# alu_slice.net
KiCad netlist of a schematic drawn in EAGLE
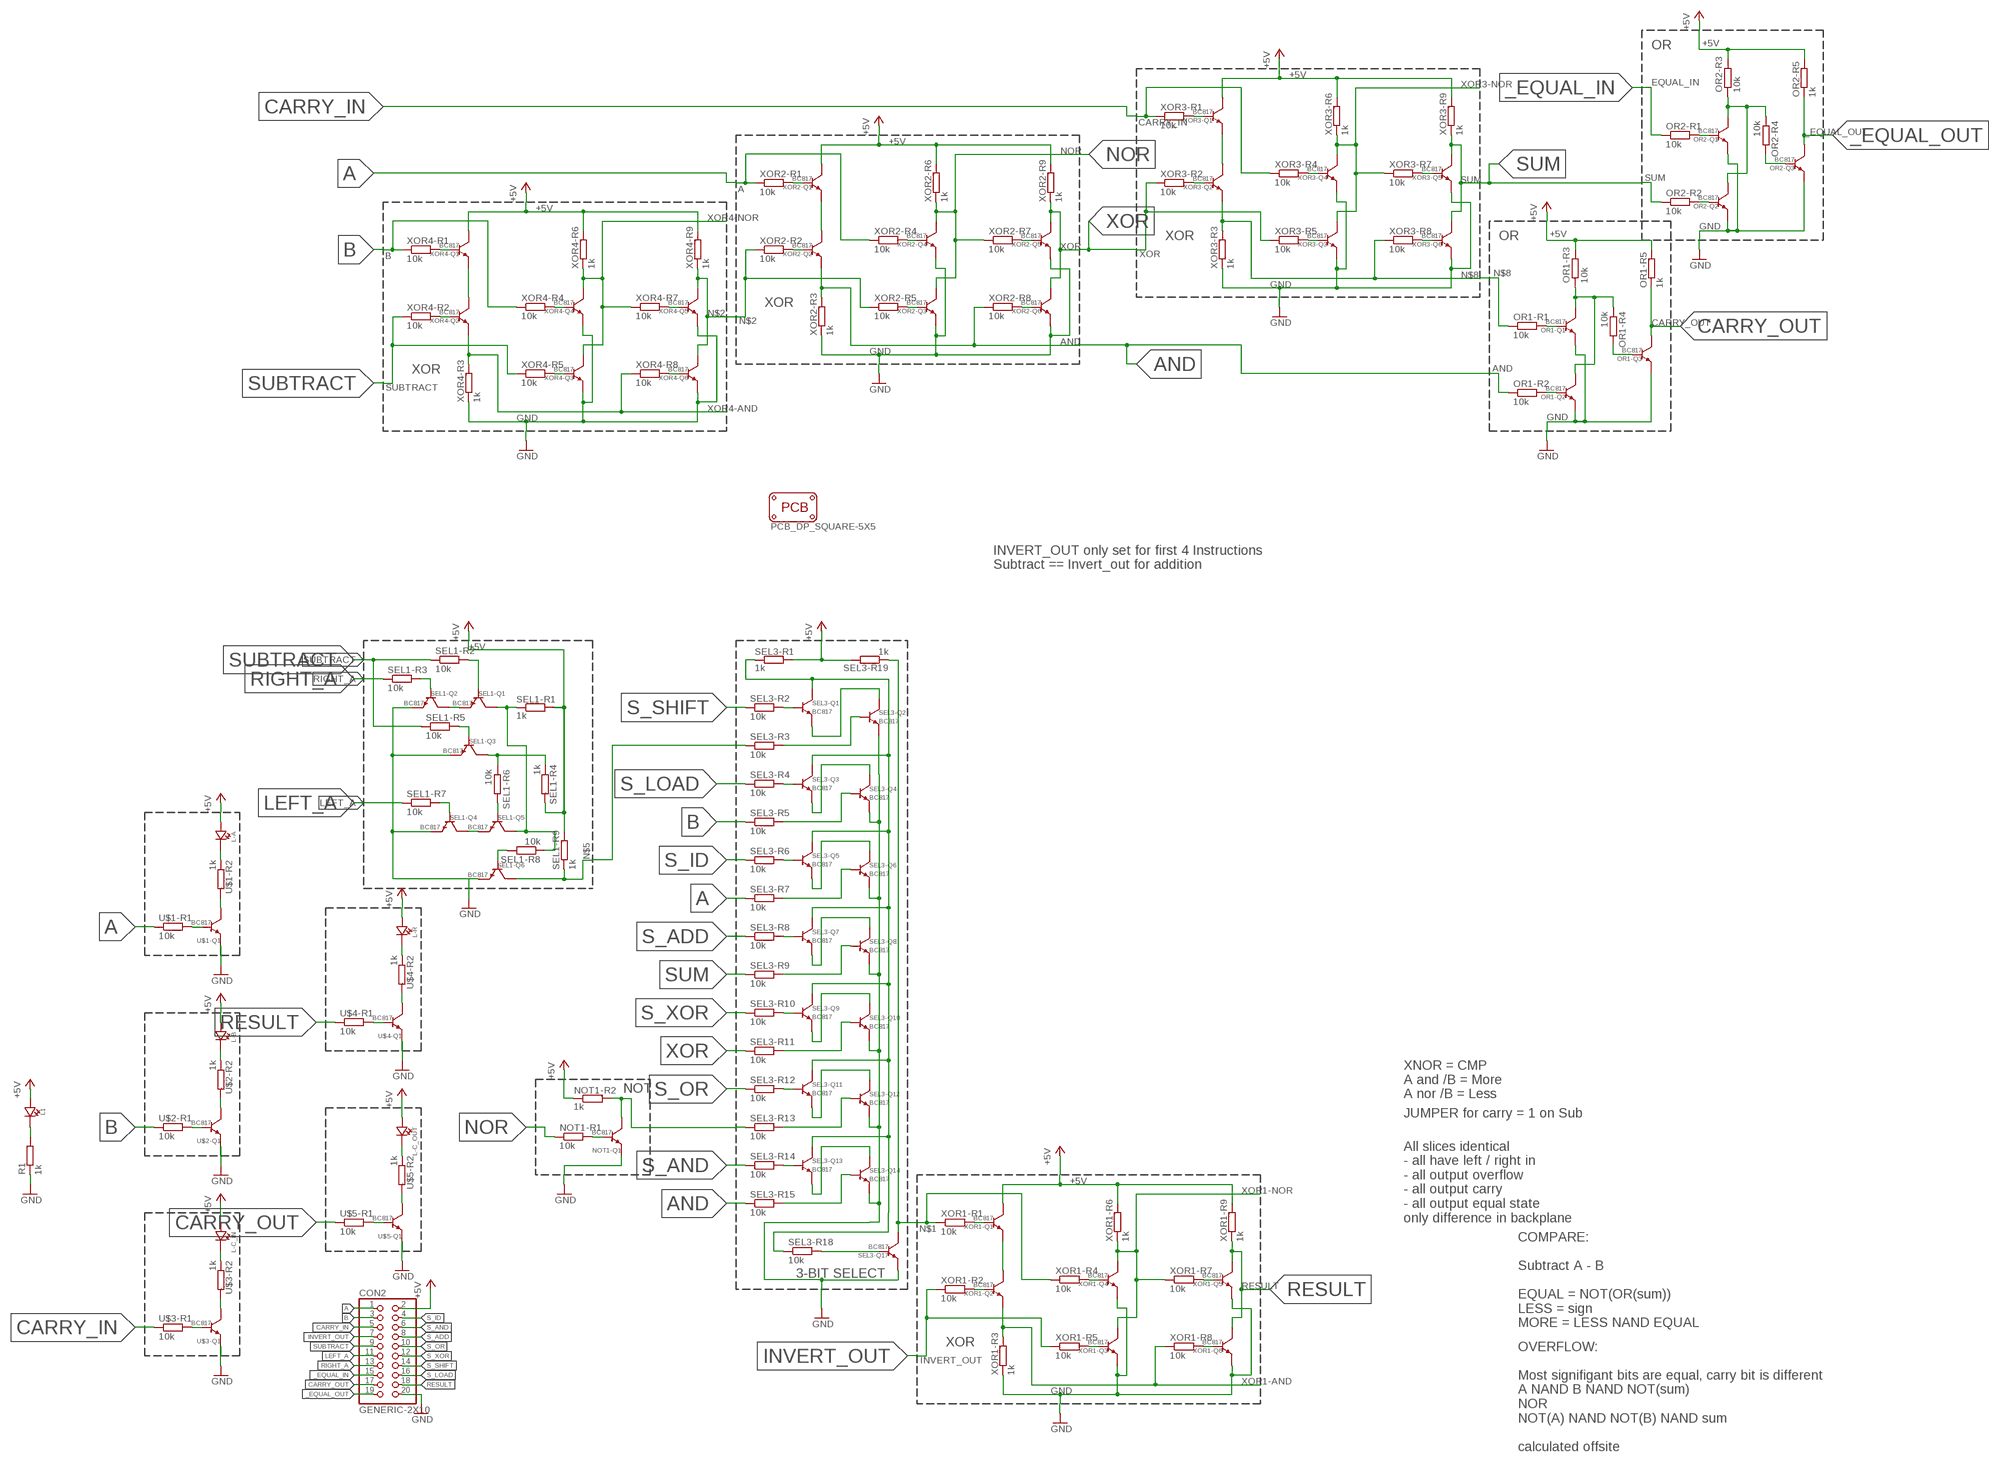
[diagram p0: schematic, sheet 1]

(export (version "E")
  (design (tool "Eeschema 10.0.6"))
  (components
    (comp (ref "CON2")
      (value "GENERIC-2X10")
      (footprint "eagle-import:PINHEADER-100MIL-2X10-EDGE")
      (libsource (lib "eagle-import") (part "GENERIC-2X10"))
    )
    (comp (ref "L-A")
      (value "LED0603")
      (footprint "eagle-import:CHIPLED_0603")
      (libsource (lib "eagle-import") (part "LED0603"))
    )
    (comp (ref "L-B")
      (value "LED0603")
      (footprint "eagle-import:CHIPLED_0603")
      (libsource (lib "eagle-import") (part "LED0603"))
    )
    (comp (ref "L-C_IN")
      (value "LED0603")
      (footprint "eagle-import:CHIPLED_0603")
      (libsource (lib "eagle-import") (part "LED0603"))
    )
    (comp (ref "L-C_OUT")
      (value "LED0603")
      (footprint "eagle-import:CHIPLED_0603")
      (libsource (lib "eagle-import") (part "LED0603"))
    )
    (comp (ref "L-R")
      (value "LED0603")
      (footprint "eagle-import:CHIPLED_0603")
      (libsource (lib "eagle-import") (part "LED0603"))
    )
    (comp (ref "L1")
      (value "LED0805")
      (footprint "eagle-import:CHIPLED_0805")
      (libsource (lib "eagle-import") (part "LED0805"))
    )
    (comp (ref "NOT1-Q1")
      (value "BC817")
      (footprint "eagle-import:SOT23")
      (libsource (lib "eagle-import") (part "TRANSISTOR-NPN-GENERIC-SOT23-BECDEFAULT"))
    )
    (comp (ref "NOT1-R1")
      (value "10k")
      (footprint "eagle-import:R0603")
      (libsource (lib "eagle-import") (part "R-EU_R0603"))
    )
    (comp (ref "NOT1-R2")
      (value "1k")
      (footprint "eagle-import:R0603-MARK")
      (libsource (lib "eagle-import") (part "R-EU-MARKEDR0603"))
    )
    (comp (ref "OR1-Q1")
      (value "BC817")
      (footprint "eagle-import:SOT23")
      (libsource (lib "eagle-import") (part "TRANSISTOR-NPN-GENERIC-SOT23-BECDEFAULT"))
    )
    (comp (ref "OR1-Q2")
      (value "BC817")
      (footprint "eagle-import:SOT23")
      (libsource (lib "eagle-import") (part "TRANSISTOR-NPN-GENERIC-SOT23-BECDEFAULT"))
    )
    (comp (ref "OR1-Q3")
      (value "BC817")
      (footprint "eagle-import:SOT23")
      (libsource (lib "eagle-import") (part "TRANSISTOR-NPN-GENERIC-SOT23-BECDEFAULT"))
    )
    (comp (ref "OR1-R1")
      (value "10k")
      (footprint "eagle-import:R0603")
      (libsource (lib "eagle-import") (part "R-EU_R0603"))
    )
    (comp (ref "OR1-R2")
      (value "10k")
      (footprint "eagle-import:R0603")
      (libsource (lib "eagle-import") (part "R-EU_R0603"))
    )
    (comp (ref "OR1-R3")
      (value "10k")
      (footprint "eagle-import:R0603")
      (libsource (lib "eagle-import") (part "R-EU_R0603"))
    )
    (comp (ref "OR1-R4")
      (value "10k")
      (footprint "eagle-import:R0603")
      (libsource (lib "eagle-import") (part "R-EU_R0603"))
    )
    (comp (ref "OR1-R5")
      (value "1k")
      (footprint "eagle-import:R0603-MARK")
      (libsource (lib "eagle-import") (part "R-EU-MARKEDR0603"))
    )
    (comp (ref "OR2-Q1")
      (value "BC817")
      (footprint "eagle-import:SOT23")
      (libsource (lib "eagle-import") (part "TRANSISTOR-NPN-GENERIC-SOT23-BECDEFAULT"))
    )
    (comp (ref "OR2-Q2")
      (value "BC817")
      (footprint "eagle-import:SOT23")
      (libsource (lib "eagle-import") (part "TRANSISTOR-NPN-GENERIC-SOT23-BECDEFAULT"))
    )
    (comp (ref "OR2-Q3")
      (value "BC817")
      (footprint "eagle-import:SOT23")
      (libsource (lib "eagle-import") (part "TRANSISTOR-NPN-GENERIC-SOT23-BECDEFAULT"))
    )
    (comp (ref "OR2-R1")
      (value "10k")
      (footprint "eagle-import:R0603")
      (libsource (lib "eagle-import") (part "R-EU_R0603"))
    )
    (comp (ref "OR2-R2")
      (value "10k")
      (footprint "eagle-import:R0603")
      (libsource (lib "eagle-import") (part "R-EU_R0603"))
    )
    (comp (ref "OR2-R3")
      (value "10k")
      (footprint "eagle-import:R0603")
      (libsource (lib "eagle-import") (part "R-EU_R0603"))
    )
    (comp (ref "OR2-R4")
      (value "10k")
      (footprint "eagle-import:R0603")
      (libsource (lib "eagle-import") (part "R-EU_R0603"))
    )
    (comp (ref "OR2-R5")
      (value "1k")
      (footprint "eagle-import:R0603-MARK")
      (libsource (lib "eagle-import") (part "R-EU-MARKEDR0603"))
    )
    (comp (ref "PCB1")
      (value "PCB_DP_SQUARE-5X5")
      (footprint "eagle-import:DP5050_V1")
      (libsource (lib "eagle-import") (part "PCB_DP_SQUARE-5X5"))
    )
    (comp (ref "R1")
      (value "1k")
      (footprint "eagle-import:R0603-MARK")
      (libsource (lib "eagle-import") (part "R-EU-MARKEDR0603"))
    )
    (comp (ref "SEL1-Q1")
      (value "BC817")
      (footprint "eagle-import:SOT23")
      (libsource (lib "eagle-import") (part "TRANSISTOR-NPN-GENERIC-SOT23-BECDEFAULT"))
    )
    (comp (ref "SEL1-Q2")
      (value "BC817")
      (footprint "eagle-import:SOT23")
      (libsource (lib "eagle-import") (part "TRANSISTOR-NPN-GENERIC-SOT23-BECDEFAULT"))
    )
    (comp (ref "SEL1-Q3")
      (value "BC817")
      (footprint "eagle-import:SOT23")
      (libsource (lib "eagle-import") (part "TRANSISTOR-NPN-GENERIC-SOT23-BECDEFAULT"))
    )
    (comp (ref "SEL1-Q4")
      (value "BC817")
      (footprint "eagle-import:SOT23")
      (libsource (lib "eagle-import") (part "TRANSISTOR-NPN-GENERIC-SOT23-BECDEFAULT"))
    )
    (comp (ref "SEL1-Q5")
      (value "BC817")
      (footprint "eagle-import:SOT23")
      (libsource (lib "eagle-import") (part "TRANSISTOR-NPN-GENERIC-SOT23-BECDEFAULT"))
    )
    (comp (ref "SEL1-Q6")
      (value "BC817")
      (footprint "eagle-import:SOT23")
      (libsource (lib "eagle-import") (part "TRANSISTOR-NPN-GENERIC-SOT23-BECDEFAULT"))
    )
    (comp (ref "SEL1-R1")
      (value "1k")
      (footprint "eagle-import:R0603-MARK")
      (libsource (lib "eagle-import") (part "R-EU-MARKEDR0603"))
    )
    (comp (ref "SEL1-R2")
      (value "10k")
      (footprint "eagle-import:R0603")
      (libsource (lib "eagle-import") (part "R-EU_R0603"))
    )
    (comp (ref "SEL1-R3")
      (value "10k")
      (footprint "eagle-import:R0603")
      (libsource (lib "eagle-import") (part "R-EU_R0603"))
    )
    (comp (ref "SEL1-R4")
      (value "1k")
      (footprint "eagle-import:R0603-MARK")
      (libsource (lib "eagle-import") (part "R-EU-MARKEDR0603"))
    )
    (comp (ref "SEL1-R5")
      (value "10k")
      (footprint "eagle-import:R0603")
      (libsource (lib "eagle-import") (part "R-EU_R0603"))
    )
    (comp (ref "SEL1-R6")
      (value "10k")
      (footprint "eagle-import:R0603")
      (libsource (lib "eagle-import") (part "R-EU_R0603"))
    )
    (comp (ref "SEL1-R7")
      (value "10k")
      (footprint "eagle-import:R0603")
      (libsource (lib "eagle-import") (part "R-EU_R0603"))
    )
    (comp (ref "SEL1-R8")
      (value "10k")
      (footprint "eagle-import:R0603")
      (libsource (lib "eagle-import") (part "R-EU_R0603"))
    )
    (comp (ref "SEL1-R9")
      (value "1k")
      (footprint "eagle-import:R0603-MARK")
      (libsource (lib "eagle-import") (part "R-EU-MARKEDR0603"))
    )
    (comp (ref "SEL3-Q1")
      (value "BC817")
      (footprint "eagle-import:SOT23")
      (libsource (lib "eagle-import") (part "TRANSISTOR-NPN-GENERIC-SOT23-BECDEFAULT"))
    )
    (comp (ref "SEL3-Q2")
      (value "BC817")
      (footprint "eagle-import:SOT23")
      (libsource (lib "eagle-import") (part "TRANSISTOR-NPN-GENERIC-SOT23-BECDEFAULT"))
    )
    (comp (ref "SEL3-Q3")
      (value "BC817")
      (footprint "eagle-import:SOT23")
      (libsource (lib "eagle-import") (part "TRANSISTOR-NPN-GENERIC-SOT23-BECDEFAULT"))
    )
    (comp (ref "SEL3-Q4")
      (value "BC817")
      (footprint "eagle-import:SOT23")
      (libsource (lib "eagle-import") (part "TRANSISTOR-NPN-GENERIC-SOT23-BECDEFAULT"))
    )
    (comp (ref "SEL3-Q5")
      (value "BC817")
      (footprint "eagle-import:SOT23")
      (libsource (lib "eagle-import") (part "TRANSISTOR-NPN-GENERIC-SOT23-BECDEFAULT"))
    )
    (comp (ref "SEL3-Q6")
      (value "BC817")
      (footprint "eagle-import:SOT23")
      (libsource (lib "eagle-import") (part "TRANSISTOR-NPN-GENERIC-SOT23-BECDEFAULT"))
    )
    (comp (ref "SEL3-Q7")
      (value "BC817")
      (footprint "eagle-import:SOT23")
      (libsource (lib "eagle-import") (part "TRANSISTOR-NPN-GENERIC-SOT23-BECDEFAULT"))
    )
    (comp (ref "SEL3-Q8")
      (value "BC817")
      (footprint "eagle-import:SOT23")
      (libsource (lib "eagle-import") (part "TRANSISTOR-NPN-GENERIC-SOT23-BECDEFAULT"))
    )
    (comp (ref "SEL3-Q9")
      (value "BC817")
      (footprint "eagle-import:SOT23")
      (libsource (lib "eagle-import") (part "TRANSISTOR-NPN-GENERIC-SOT23-BECDEFAULT"))
    )
    (comp (ref "SEL3-Q10")
      (value "BC817")
      (footprint "eagle-import:SOT23")
      (libsource (lib "eagle-import") (part "TRANSISTOR-NPN-GENERIC-SOT23-BECDEFAULT"))
    )
    (comp (ref "SEL3-Q11")
      (value "BC817")
      (footprint "eagle-import:SOT23")
      (libsource (lib "eagle-import") (part "TRANSISTOR-NPN-GENERIC-SOT23-BECDEFAULT"))
    )
    (comp (ref "SEL3-Q12")
      (value "BC817")
      (footprint "eagle-import:SOT23")
      (libsource (lib "eagle-import") (part "TRANSISTOR-NPN-GENERIC-SOT23-BECDEFAULT"))
    )
    (comp (ref "SEL3-Q13")
      (value "BC817")
      (footprint "eagle-import:SOT23")
      (libsource (lib "eagle-import") (part "TRANSISTOR-NPN-GENERIC-SOT23-BECDEFAULT"))
    )
    (comp (ref "SEL3-Q14")
      (value "BC817")
      (footprint "eagle-import:SOT23")
      (libsource (lib "eagle-import") (part "TRANSISTOR-NPN-GENERIC-SOT23-BECDEFAULT"))
    )
    (comp (ref "SEL3-Q17")
      (value "BC817")
      (footprint "eagle-import:SOT23")
      (libsource (lib "eagle-import") (part "TRANSISTOR-NPN-GENERIC-SOT23-BECDEFAULT"))
    )
    (comp (ref "SEL3-R1")
      (value "1k")
      (footprint "eagle-import:R0603-MARK")
      (libsource (lib "eagle-import") (part "R-EU-MARKEDR0603"))
    )
    (comp (ref "SEL3-R2")
      (value "10k")
      (footprint "eagle-import:R0603")
      (libsource (lib "eagle-import") (part "R-EU_R0603"))
    )
    (comp (ref "SEL3-R3")
      (value "10k")
      (footprint "eagle-import:R0603")
      (libsource (lib "eagle-import") (part "R-EU_R0603"))
    )
    (comp (ref "SEL3-R4")
      (value "10k")
      (footprint "eagle-import:R0603")
      (libsource (lib "eagle-import") (part "R-EU_R0603"))
    )
    (comp (ref "SEL3-R5")
      (value "10k")
      (footprint "eagle-import:R0603")
      (libsource (lib "eagle-import") (part "R-EU_R0603"))
    )
    (comp (ref "SEL3-R6")
      (value "10k")
      (footprint "eagle-import:R0603")
      (libsource (lib "eagle-import") (part "R-EU_R0603"))
    )
    (comp (ref "SEL3-R7")
      (value "10k")
      (footprint "eagle-import:R0603")
      (libsource (lib "eagle-import") (part "R-EU_R0603"))
    )
    (comp (ref "SEL3-R8")
      (value "10k")
      (footprint "eagle-import:R0603")
      (libsource (lib "eagle-import") (part "R-EU_R0603"))
    )
    (comp (ref "SEL3-R9")
      (value "10k")
      (footprint "eagle-import:R0603")
      (libsource (lib "eagle-import") (part "R-EU_R0603"))
    )
    (comp (ref "SEL3-R10")
      (value "10k")
      (footprint "eagle-import:R0603")
      (libsource (lib "eagle-import") (part "R-EU_R0603"))
    )
    (comp (ref "SEL3-R11")
      (value "10k")
      (footprint "eagle-import:R0603")
      (libsource (lib "eagle-import") (part "R-EU_R0603"))
    )
    (comp (ref "SEL3-R12")
      (value "10k")
      (footprint "eagle-import:R0603")
      (libsource (lib "eagle-import") (part "R-EU_R0603"))
    )
    (comp (ref "SEL3-R13")
      (value "10k")
      (footprint "eagle-import:R0603")
      (libsource (lib "eagle-import") (part "R-EU_R0603"))
    )
    (comp (ref "SEL3-R14")
      (value "10k")
      (footprint "eagle-import:R0603")
      (libsource (lib "eagle-import") (part "R-EU_R0603"))
    )
    (comp (ref "SEL3-R15")
      (value "10k")
      (footprint "eagle-import:R0603")
      (libsource (lib "eagle-import") (part "R-EU_R0603"))
    )
    (comp (ref "SEL3-R18")
      (value "10k")
      (footprint "eagle-import:R0603")
      (libsource (lib "eagle-import") (part "R-EU_R0603"))
    )
    (comp (ref "SEL3-R19")
      (value "1k")
      (footprint "eagle-import:R0603-MARK")
      (libsource (lib "eagle-import") (part "R-EU-MARKEDR0603"))
    )
    (comp (ref "U$1-Q1")
      (value "BC817")
      (footprint "eagle-import:SOT23")
      (libsource (lib "eagle-import") (part "TRANSISTOR-NPN-GENERIC-SOT23-BECDEFAULT"))
    )
    (comp (ref "U$1-R1")
      (value "10k")
      (footprint "eagle-import:R0603")
      (libsource (lib "eagle-import") (part "R-EU_R0603"))
    )
    (comp (ref "U$1-R2")
      (value "1k")
      (footprint "eagle-import:R0603-MARK")
      (libsource (lib "eagle-import") (part "R-EU-MARKEDR0603"))
    )
    (comp (ref "U$2-Q1")
      (value "BC817")
      (footprint "eagle-import:SOT23")
      (libsource (lib "eagle-import") (part "TRANSISTOR-NPN-GENERIC-SOT23-BECDEFAULT"))
    )
    (comp (ref "U$2-R1")
      (value "10k")
      (footprint "eagle-import:R0603")
      (libsource (lib "eagle-import") (part "R-EU_R0603"))
    )
    (comp (ref "U$2-R2")
      (value "1k")
      (footprint "eagle-import:R0603-MARK")
      (libsource (lib "eagle-import") (part "R-EU-MARKEDR0603"))
    )
    (comp (ref "U$3-Q1")
      (value "BC817")
      (footprint "eagle-import:SOT23")
      (libsource (lib "eagle-import") (part "TRANSISTOR-NPN-GENERIC-SOT23-BECDEFAULT"))
    )
    (comp (ref "U$3-R1")
      (value "10k")
      (footprint "eagle-import:R0603")
      (libsource (lib "eagle-import") (part "R-EU_R0603"))
    )
    (comp (ref "U$3-R2")
      (value "1k")
      (footprint "eagle-import:R0603-MARK")
      (libsource (lib "eagle-import") (part "R-EU-MARKEDR0603"))
    )
    (comp (ref "U$4-Q1")
      (value "BC817")
      (footprint "eagle-import:SOT23")
      (libsource (lib "eagle-import") (part "TRANSISTOR-NPN-GENERIC-SOT23-BECDEFAULT"))
    )
    (comp (ref "U$4-R1")
      (value "10k")
      (footprint "eagle-import:R0603")
      (libsource (lib "eagle-import") (part "R-EU_R0603"))
    )
    (comp (ref "U$4-R2")
      (value "1k")
      (footprint "eagle-import:R0603-MARK")
      (libsource (lib "eagle-import") (part "R-EU-MARKEDR0603"))
    )
    (comp (ref "U$5-Q1")
      (value "BC817")
      (footprint "eagle-import:SOT23")
      (libsource (lib "eagle-import") (part "TRANSISTOR-NPN-GENERIC-SOT23-BECDEFAULT"))
    )
    (comp (ref "U$5-R1")
      (value "10k")
      (footprint "eagle-import:R0603")
      (libsource (lib "eagle-import") (part "R-EU_R0603"))
    )
    (comp (ref "U$5-R2")
      (value "1k")
      (footprint "eagle-import:R0603-MARK")
      (libsource (lib "eagle-import") (part "R-EU-MARKEDR0603"))
    )
    (comp (ref "XOR1-Q1")
      (value "BC817")
      (footprint "eagle-import:SOT23")
      (libsource (lib "eagle-import") (part "TRANSISTOR-NPN-GENERIC-SOT23-BECDEFAULT"))
    )
    (comp (ref "XOR1-Q2")
      (value "BC817")
      (footprint "eagle-import:SOT23")
      (libsource (lib "eagle-import") (part "TRANSISTOR-NPN-GENERIC-SOT23-BECDEFAULT"))
    )
    (comp (ref "XOR1-Q3")
      (value "BC817")
      (footprint "eagle-import:SOT23")
      (libsource (lib "eagle-import") (part "TRANSISTOR-NPN-GENERIC-SOT23-BECDEFAULT"))
    )
    (comp (ref "XOR1-Q4")
      (value "BC817")
      (footprint "eagle-import:SOT23")
      (libsource (lib "eagle-import") (part "TRANSISTOR-NPN-GENERIC-SOT23-BECDEFAULT"))
    )
    (comp (ref "XOR1-Q5")
      (value "BC817")
      (footprint "eagle-import:SOT23")
      (libsource (lib "eagle-import") (part "TRANSISTOR-NPN-GENERIC-SOT23-BECDEFAULT"))
    )
    (comp (ref "XOR1-Q6")
      (value "BC817")
      (footprint "eagle-import:SOT23")
      (libsource (lib "eagle-import") (part "TRANSISTOR-NPN-GENERIC-SOT23-BECDEFAULT"))
    )
    (comp (ref "XOR1-R1")
      (value "10k")
      (footprint "eagle-import:R0603")
      (libsource (lib "eagle-import") (part "R-EU_R0603"))
    )
    (comp (ref "XOR1-R2")
      (value "10k")
      (footprint "eagle-import:R0603")
      (libsource (lib "eagle-import") (part "R-EU_R0603"))
    )
    (comp (ref "XOR1-R3")
      (value "1k")
      (footprint "eagle-import:R0603-MARK")
      (libsource (lib "eagle-import") (part "R-EU-MARKEDR0603"))
    )
    (comp (ref "XOR1-R4")
      (value "10k")
      (footprint "eagle-import:R0603")
      (libsource (lib "eagle-import") (part "R-EU_R0603"))
    )
    (comp (ref "XOR1-R5")
      (value "10k")
      (footprint "eagle-import:R0603")
      (libsource (lib "eagle-import") (part "R-EU_R0603"))
    )
    (comp (ref "XOR1-R6")
      (value "1k")
      (footprint "eagle-import:R0603-MARK")
      (libsource (lib "eagle-import") (part "R-EU-MARKEDR0603"))
    )
    (comp (ref "XOR1-R7")
      (value "10k")
      (footprint "eagle-import:R0603")
      (libsource (lib "eagle-import") (part "R-EU_R0603"))
    )
    (comp (ref "XOR1-R8")
      (value "10k")
      (footprint "eagle-import:R0603")
      (libsource (lib "eagle-import") (part "R-EU_R0603"))
    )
    (comp (ref "XOR1-R9")
      (value "1k")
      (footprint "eagle-import:R0603-MARK")
      (libsource (lib "eagle-import") (part "R-EU-MARKEDR0603"))
    )
    (comp (ref "XOR2-Q1")
      (value "BC817")
      (footprint "eagle-import:SOT23")
      (libsource (lib "eagle-import") (part "TRANSISTOR-NPN-GENERIC-SOT23-BECDEFAULT"))
    )
    (comp (ref "XOR2-Q2")
      (value "BC817")
      (footprint "eagle-import:SOT23")
      (libsource (lib "eagle-import") (part "TRANSISTOR-NPN-GENERIC-SOT23-BECDEFAULT"))
    )
    (comp (ref "XOR2-Q3")
      (value "BC817")
      (footprint "eagle-import:SOT23")
      (libsource (lib "eagle-import") (part "TRANSISTOR-NPN-GENERIC-SOT23-BECDEFAULT"))
    )
    (comp (ref "XOR2-Q4")
      (value "BC817")
      (footprint "eagle-import:SOT23")
      (libsource (lib "eagle-import") (part "TRANSISTOR-NPN-GENERIC-SOT23-BECDEFAULT"))
    )
    (comp (ref "XOR2-Q5")
      (value "BC817")
      (footprint "eagle-import:SOT23")
      (libsource (lib "eagle-import") (part "TRANSISTOR-NPN-GENERIC-SOT23-BECDEFAULT"))
    )
    (comp (ref "XOR2-Q6")
      (value "BC817")
      (footprint "eagle-import:SOT23")
      (libsource (lib "eagle-import") (part "TRANSISTOR-NPN-GENERIC-SOT23-BECDEFAULT"))
    )
    (comp (ref "XOR2-R1")
      (value "10k")
      (footprint "eagle-import:R0603")
      (libsource (lib "eagle-import") (part "R-EU_R0603"))
    )
    (comp (ref "XOR2-R2")
      (value "10k")
      (footprint "eagle-import:R0603")
      (libsource (lib "eagle-import") (part "R-EU_R0603"))
    )
    (comp (ref "XOR2-R3")
      (value "1k")
      (footprint "eagle-import:R0603-MARK")
      (libsource (lib "eagle-import") (part "R-EU-MARKEDR0603"))
    )
    (comp (ref "XOR2-R4")
      (value "10k")
      (footprint "eagle-import:R0603")
      (libsource (lib "eagle-import") (part "R-EU_R0603"))
    )
    (comp (ref "XOR2-R5")
      (value "10k")
      (footprint "eagle-import:R0603")
      (libsource (lib "eagle-import") (part "R-EU_R0603"))
    )
    (comp (ref "XOR2-R6")
      (value "1k")
      (footprint "eagle-import:R0603-MARK")
      (libsource (lib "eagle-import") (part "R-EU-MARKEDR0603"))
    )
    (comp (ref "XOR2-R7")
      (value "10k")
      (footprint "eagle-import:R0603")
      (libsource (lib "eagle-import") (part "R-EU_R0603"))
    )
    (comp (ref "XOR2-R8")
      (value "10k")
      (footprint "eagle-import:R0603")
      (libsource (lib "eagle-import") (part "R-EU_R0603"))
    )
    (comp (ref "XOR2-R9")
      (value "1k")
      (footprint "eagle-import:R0603-MARK")
      (libsource (lib "eagle-import") (part "R-EU-MARKEDR0603"))
    )
    (comp (ref "XOR3-Q1")
      (value "BC817")
      (footprint "eagle-import:SOT23")
      (libsource (lib "eagle-import") (part "TRANSISTOR-NPN-GENERIC-SOT23-BECDEFAULT"))
    )
    (comp (ref "XOR3-Q2")
      (value "BC817")
      (footprint "eagle-import:SOT23")
      (libsource (lib "eagle-import") (part "TRANSISTOR-NPN-GENERIC-SOT23-BECDEFAULT"))
    )
    (comp (ref "XOR3-Q3")
      (value "BC817")
      (footprint "eagle-import:SOT23")
      (libsource (lib "eagle-import") (part "TRANSISTOR-NPN-GENERIC-SOT23-BECDEFAULT"))
    )
    (comp (ref "XOR3-Q4")
      (value "BC817")
      (footprint "eagle-import:SOT23")
      (libsource (lib "eagle-import") (part "TRANSISTOR-NPN-GENERIC-SOT23-BECDEFAULT"))
    )
    (comp (ref "XOR3-Q5")
      (value "BC817")
      (footprint "eagle-import:SOT23")
      (libsource (lib "eagle-import") (part "TRANSISTOR-NPN-GENERIC-SOT23-BECDEFAULT"))
    )
    (comp (ref "XOR3-Q6")
      (value "BC817")
      (footprint "eagle-import:SOT23")
      (libsource (lib "eagle-import") (part "TRANSISTOR-NPN-GENERIC-SOT23-BECDEFAULT"))
    )
    (comp (ref "XOR3-R1")
      (value "10k")
      (footprint "eagle-import:R0603")
      (libsource (lib "eagle-import") (part "R-EU_R0603"))
    )
    (comp (ref "XOR3-R2")
      (value "10k")
      (footprint "eagle-import:R0603")
      (libsource (lib "eagle-import") (part "R-EU_R0603"))
    )
    (comp (ref "XOR3-R3")
      (value "1k")
      (footprint "eagle-import:R0603-MARK")
      (libsource (lib "eagle-import") (part "R-EU-MARKEDR0603"))
    )
    (comp (ref "XOR3-R4")
      (value "10k")
      (footprint "eagle-import:R0603")
      (libsource (lib "eagle-import") (part "R-EU_R0603"))
    )
    (comp (ref "XOR3-R5")
      (value "10k")
      (footprint "eagle-import:R0603")
      (libsource (lib "eagle-import") (part "R-EU_R0603"))
    )
    (comp (ref "XOR3-R6")
      (value "1k")
      (footprint "eagle-import:R0603-MARK")
      (libsource (lib "eagle-import") (part "R-EU-MARKEDR0603"))
    )
    (comp (ref "XOR3-R7")
      (value "10k")
      (footprint "eagle-import:R0603")
      (libsource (lib "eagle-import") (part "R-EU_R0603"))
    )
    (comp (ref "XOR3-R8")
      (value "10k")
      (footprint "eagle-import:R0603")
      (libsource (lib "eagle-import") (part "R-EU_R0603"))
    )
    (comp (ref "XOR3-R9")
      (value "1k")
      (footprint "eagle-import:R0603-MARK")
      (libsource (lib "eagle-import") (part "R-EU-MARKEDR0603"))
    )
    (comp (ref "XOR4-Q1")
      (value "BC817")
      (footprint "eagle-import:SOT23")
      (libsource (lib "eagle-import") (part "TRANSISTOR-NPN-GENERIC-SOT23-BECDEFAULT"))
    )
    (comp (ref "XOR4-Q2")
      (value "BC817")
      (footprint "eagle-import:SOT23")
      (libsource (lib "eagle-import") (part "TRANSISTOR-NPN-GENERIC-SOT23-BECDEFAULT"))
    )
    (comp (ref "XOR4-Q3")
      (value "BC817")
      (footprint "eagle-import:SOT23")
      (libsource (lib "eagle-import") (part "TRANSISTOR-NPN-GENERIC-SOT23-BECDEFAULT"))
    )
    (comp (ref "XOR4-Q4")
      (value "BC817")
      (footprint "eagle-import:SOT23")
      (libsource (lib "eagle-import") (part "TRANSISTOR-NPN-GENERIC-SOT23-BECDEFAULT"))
    )
    (comp (ref "XOR4-Q5")
      (value "BC817")
      (footprint "eagle-import:SOT23")
      (libsource (lib "eagle-import") (part "TRANSISTOR-NPN-GENERIC-SOT23-BECDEFAULT"))
    )
    (comp (ref "XOR4-Q6")
      (value "BC817")
      (footprint "eagle-import:SOT23")
      (libsource (lib "eagle-import") (part "TRANSISTOR-NPN-GENERIC-SOT23-BECDEFAULT"))
    )
    (comp (ref "XOR4-R1")
      (value "10k")
      (footprint "eagle-import:R0603")
      (libsource (lib "eagle-import") (part "R-EU_R0603"))
    )
    (comp (ref "XOR4-R2")
      (value "10k")
      (footprint "eagle-import:R0603")
      (libsource (lib "eagle-import") (part "R-EU_R0603"))
    )
    (comp (ref "XOR4-R3")
      (value "1k")
      (footprint "eagle-import:R0603-MARK")
      (libsource (lib "eagle-import") (part "R-EU-MARKEDR0603"))
    )
    (comp (ref "XOR4-R4")
      (value "10k")
      (footprint "eagle-import:R0603")
      (libsource (lib "eagle-import") (part "R-EU_R0603"))
    )
    (comp (ref "XOR4-R5")
      (value "10k")
      (footprint "eagle-import:R0603")
      (libsource (lib "eagle-import") (part "R-EU_R0603"))
    )
    (comp (ref "XOR4-R6")
      (value "1k")
      (footprint "eagle-import:R0603-MARK")
      (libsource (lib "eagle-import") (part "R-EU-MARKEDR0603"))
    )
    (comp (ref "XOR4-R7")
      (value "10k")
      (footprint "eagle-import:R0603")
      (libsource (lib "eagle-import") (part "R-EU_R0603"))
    )
    (comp (ref "XOR4-R8")
      (value "10k")
      (footprint "eagle-import:R0603")
      (libsource (lib "eagle-import") (part "R-EU_R0603"))
    )
    (comp (ref "XOR4-R9")
      (value "1k")
      (footprint "eagle-import:R0603-MARK")
      (libsource (lib "eagle-import") (part "R-EU-MARKEDR0603"))
    )
  )
  (nets
    (net (code "1") (name "+5V") (class "Default")
      (node (ref "CON2") (pin "2") (pinfunction "2_2") (pintype "passive"))
      (node (ref "L-A") (pin "A") (pinfunction "A_A") (pintype "bidirectional"))
      (node (ref "L-B") (pin "A") (pinfunction "A_A") (pintype "bidirectional"))
      (node (ref "L-C_IN") (pin "A") (pinfunction "A_A") (pintype "bidirectional"))
      (node (ref "L-C_OUT") (pin "A") (pinfunction "A_A") (pintype "bidirectional"))
      (node (ref "L-R") (pin "A") (pinfunction "A_A") (pintype "bidirectional"))
      (node (ref "L1") (pin "A") (pinfunction "A_A") (pintype "bidirectional"))
      (node (ref "NOT1-R2") (pin "1") (pinfunction "1_1") (pintype "passive"))
      (node (ref "OR1-R3") (pin "2") (pinfunction "2_2") (pintype "passive"))
      (node (ref "OR1-R5") (pin "2") (pinfunction "2_2") (pintype "passive"))
      (node (ref "OR2-R3") (pin "2") (pinfunction "2_2") (pintype "passive"))
      (node (ref "OR2-R5") (pin "2") (pinfunction "2_2") (pintype "passive"))
      (node (ref "SEL1-R1") (pin "2") (pinfunction "2_2") (pintype "passive"))
      (node (ref "SEL1-R4") (pin "2") (pinfunction "2_2") (pintype "passive"))
      (node (ref "SEL1-R9") (pin "2") (pinfunction "2_2") (pintype "passive"))
      (node (ref "SEL3-R1") (pin "2") (pinfunction "2_2") (pintype "passive"))
      (node (ref "SEL3-R19") (pin "2") (pinfunction "2_2") (pintype "passive"))
      (node (ref "XOR1-Q1") (pin "P$3") (pinfunction "COLLECTOR_P$3") (pintype "bidirectional"))
      (node (ref "XOR1-R6") (pin "2") (pinfunction "2_2") (pintype "passive"))
      (node (ref "XOR1-R9") (pin "2") (pinfunction "2_2") (pintype "passive"))
      (node (ref "XOR2-Q1") (pin "P$3") (pinfunction "COLLECTOR_P$3") (pintype "bidirectional"))
      (node (ref "XOR2-R6") (pin "2") (pinfunction "2_2") (pintype "passive"))
      (node (ref "XOR2-R9") (pin "2") (pinfunction "2_2") (pintype "passive"))
      (node (ref "XOR3-Q1") (pin "P$3") (pinfunction "COLLECTOR_P$3") (pintype "bidirectional"))
      (node (ref "XOR3-R6") (pin "2") (pinfunction "2_2") (pintype "passive"))
      (node (ref "XOR3-R9") (pin "2") (pinfunction "2_2") (pintype "passive"))
      (node (ref "XOR4-Q1") (pin "P$3") (pinfunction "COLLECTOR_P$3") (pintype "bidirectional"))
      (node (ref "XOR4-R6") (pin "2") (pinfunction "2_2") (pintype "passive"))
      (node (ref "XOR4-R9") (pin "2") (pinfunction "2_2") (pintype "passive"))
    )
    (net (code "2") (name "/N$1") (class "Default")
      (node (ref "SEL3-Q17") (pin "P$3") (pinfunction "COLLECTOR_P$3") (pintype "bidirectional"))
      (node (ref "SEL3-R19") (pin "1") (pinfunction "1_1") (pintype "passive"))
      (node (ref "XOR1-R1") (pin "1") (pinfunction "1_1") (pintype "passive"))
      (node (ref "XOR1-R4") (pin "1") (pinfunction "1_1") (pintype "passive"))
    )
    (net (code "3") (name "/N$2") (class "Default")
      (node (ref "XOR2-R2") (pin "1") (pinfunction "1_1") (pintype "passive"))
      (node (ref "XOR2-R5") (pin "1") (pinfunction "1_1") (pintype "passive"))
      (node (ref "XOR4-Q5") (pin "P$3") (pinfunction "COLLECTOR_P$3") (pintype "bidirectional"))
      (node (ref "XOR4-Q6") (pin "P$3") (pinfunction "COLLECTOR_P$3") (pintype "bidirectional"))
      (node (ref "XOR4-R9") (pin "1") (pinfunction "1_1") (pintype "passive"))
    )
    (net (code "4") (name "/N$5") (class "Default")
      (node (ref "SEL1-Q6") (pin "P$3") (pinfunction "COLLECTOR_P$3") (pintype "bidirectional"))
      (node (ref "SEL1-R9") (pin "1") (pinfunction "1_1") (pintype "passive"))
      (node (ref "SEL3-R3") (pin "1") (pinfunction "1_1") (pintype "passive"))
    )
    (net (code "5") (name "/N$8") (class "Default")
      (node (ref "OR1-R1") (pin "1") (pinfunction "1_1") (pintype "passive"))
      (node (ref "XOR3-Q2") (pin "P$2") (pinfunction "EMITTER_P$2") (pintype "bidirectional"))
      (node (ref "XOR3-R3") (pin "2") (pinfunction "2_2") (pintype "passive"))
      (node (ref "XOR3-R8") (pin "1") (pinfunction "1_1") (pintype "passive"))
    )
    (net (code "6") (name "/XOR1-AND") (class "Default")
      (node (ref "XOR1-Q2") (pin "P$2") (pinfunction "EMITTER_P$2") (pintype "bidirectional"))
      (node (ref "XOR1-R3") (pin "2") (pinfunction "2_2") (pintype "passive"))
      (node (ref "XOR1-R8") (pin "1") (pinfunction "1_1") (pintype "passive"))
    )
    (net (code "7") (name "/XOR1-NOR") (class "Default")
      (node (ref "XOR1-Q3") (pin "P$3") (pinfunction "COLLECTOR_P$3") (pintype "bidirectional"))
      (node (ref "XOR1-Q4") (pin "P$3") (pinfunction "COLLECTOR_P$3") (pintype "bidirectional"))
      (node (ref "XOR1-R6") (pin "1") (pinfunction "1_1") (pintype "passive"))
      (node (ref "XOR1-R7") (pin "1") (pinfunction "1_1") (pintype "passive"))
    )
    (net (code "8") (name "/XOR3-NOR") (class "Default")
      (node (ref "XOR3-Q3") (pin "P$3") (pinfunction "COLLECTOR_P$3") (pintype "bidirectional"))
      (node (ref "XOR3-Q4") (pin "P$3") (pinfunction "COLLECTOR_P$3") (pintype "bidirectional"))
      (node (ref "XOR3-R6") (pin "1") (pinfunction "1_1") (pintype "passive"))
      (node (ref "XOR3-R7") (pin "1") (pinfunction "1_1") (pintype "passive"))
    )
    (net (code "9") (name "/XOR4-AND") (class "Default")
      (node (ref "XOR4-Q2") (pin "P$2") (pinfunction "EMITTER_P$2") (pintype "bidirectional"))
      (node (ref "XOR4-R3") (pin "2") (pinfunction "2_2") (pintype "passive"))
      (node (ref "XOR4-R8") (pin "1") (pinfunction "1_1") (pintype "passive"))
    )
    (net (code "10") (name "/XOR4-NOR") (class "Default")
      (node (ref "XOR4-Q3") (pin "P$3") (pinfunction "COLLECTOR_P$3") (pintype "bidirectional"))
      (node (ref "XOR4-Q4") (pin "P$3") (pinfunction "COLLECTOR_P$3") (pintype "bidirectional"))
      (node (ref "XOR4-R6") (pin "1") (pinfunction "1_1") (pintype "passive"))
      (node (ref "XOR4-R7") (pin "1") (pinfunction "1_1") (pintype "passive"))
    )
    (net (code "11") (name "A") (class "Default")
      (node (ref "CON2") (pin "1") (pinfunction "1_1") (pintype "passive"))
      (node (ref "SEL3-R7") (pin "1") (pinfunction "1_1") (pintype "passive"))
      (node (ref "U$1-R1") (pin "1") (pinfunction "1_1") (pintype "passive"))
      (node (ref "XOR2-R1") (pin "1") (pinfunction "1_1") (pintype "passive"))
      (node (ref "XOR2-R4") (pin "1") (pinfunction "1_1") (pintype "passive"))
    )
    (net (code "12") (name "AND") (class "Default")
      (node (ref "OR1-R2") (pin "1") (pinfunction "1_1") (pintype "passive"))
      (node (ref "SEL3-R15") (pin "1") (pinfunction "1_1") (pintype "passive"))
      (node (ref "XOR2-Q2") (pin "P$2") (pinfunction "EMITTER_P$2") (pintype "bidirectional"))
      (node (ref "XOR2-R3") (pin "2") (pinfunction "2_2") (pintype "passive"))
      (node (ref "XOR2-R8") (pin "1") (pinfunction "1_1") (pintype "passive"))
    )
    (net (code "13") (name "B") (class "Default")
      (node (ref "CON2") (pin "3") (pinfunction "3_3") (pintype "passive"))
      (node (ref "SEL3-R5") (pin "1") (pinfunction "1_1") (pintype "passive"))
      (node (ref "U$2-R1") (pin "1") (pinfunction "1_1") (pintype "passive"))
      (node (ref "XOR4-R1") (pin "1") (pinfunction "1_1") (pintype "passive"))
      (node (ref "XOR4-R4") (pin "1") (pinfunction "1_1") (pintype "passive"))
    )
    (net (code "14") (name "CARRY_IN") (class "Default")
      (node (ref "CON2") (pin "5") (pinfunction "5_5") (pintype "passive"))
      (node (ref "U$3-R1") (pin "1") (pinfunction "1_1") (pintype "passive"))
      (node (ref "XOR3-R1") (pin "1") (pinfunction "1_1") (pintype "passive"))
      (node (ref "XOR3-R4") (pin "1") (pinfunction "1_1") (pintype "passive"))
    )
    (net (code "15") (name "CARRY_OUT") (class "Default")
      (node (ref "CON2") (pin "17") (pinfunction "17_17") (pintype "passive"))
      (node (ref "OR1-Q3") (pin "P$3") (pinfunction "COLLECTOR_P$3") (pintype "bidirectional"))
      (node (ref "OR1-R5") (pin "1") (pinfunction "1_1") (pintype "passive"))
      (node (ref "U$5-R1") (pin "1") (pinfunction "1_1") (pintype "passive"))
    )
    (net (code "16") (name "GND") (class "Default")
      (node (ref "CON2") (pin "20") (pinfunction "20_20") (pintype "passive"))
      (node (ref "NOT1-Q1") (pin "P$2") (pinfunction "EMITTER_P$2") (pintype "bidirectional"))
      (node (ref "OR1-Q1") (pin "P$2") (pinfunction "EMITTER_P$2") (pintype "bidirectional"))
      (node (ref "OR1-Q2") (pin "P$2") (pinfunction "EMITTER_P$2") (pintype "bidirectional"))
      (node (ref "OR1-Q3") (pin "P$2") (pinfunction "EMITTER_P$2") (pintype "bidirectional"))
      (node (ref "OR2-Q1") (pin "P$2") (pinfunction "EMITTER_P$2") (pintype "bidirectional"))
      (node (ref "OR2-Q2") (pin "P$2") (pinfunction "EMITTER_P$2") (pintype "bidirectional"))
      (node (ref "OR2-Q3") (pin "P$2") (pinfunction "EMITTER_P$2") (pintype "bidirectional"))
      (node (ref "R1") (pin "1") (pinfunction "1_1") (pintype "passive"))
      (node (ref "SEL1-Q2") (pin "P$2") (pinfunction "EMITTER_P$2") (pintype "bidirectional"))
      (node (ref "SEL1-Q3") (pin "P$2") (pinfunction "EMITTER_P$2") (pintype "bidirectional"))
      (node (ref "SEL1-Q4") (pin "P$2") (pinfunction "EMITTER_P$2") (pintype "bidirectional"))
      (node (ref "SEL1-Q6") (pin "P$2") (pinfunction "EMITTER_P$2") (pintype "bidirectional"))
      (node (ref "SEL3-Q10") (pin "P$2") (pinfunction "EMITTER_P$2") (pintype "bidirectional"))
      (node (ref "SEL3-Q12") (pin "P$2") (pinfunction "EMITTER_P$2") (pintype "bidirectional"))
      (node (ref "SEL3-Q14") (pin "P$2") (pinfunction "EMITTER_P$2") (pintype "bidirectional"))
      (node (ref "SEL3-Q17") (pin "P$2") (pinfunction "EMITTER_P$2") (pintype "bidirectional"))
      (node (ref "SEL3-Q2") (pin "P$2") (pinfunction "EMITTER_P$2") (pintype "bidirectional"))
      (node (ref "SEL3-Q4") (pin "P$2") (pinfunction "EMITTER_P$2") (pintype "bidirectional"))
      (node (ref "SEL3-Q6") (pin "P$2") (pinfunction "EMITTER_P$2") (pintype "bidirectional"))
      (node (ref "SEL3-Q8") (pin "P$2") (pinfunction "EMITTER_P$2") (pintype "bidirectional"))
      (node (ref "U$1-Q1") (pin "P$2") (pinfunction "EMITTER_P$2") (pintype "bidirectional"))
      (node (ref "U$2-Q1") (pin "P$2") (pinfunction "EMITTER_P$2") (pintype "bidirectional"))
      (node (ref "U$3-Q1") (pin "P$2") (pinfunction "EMITTER_P$2") (pintype "bidirectional"))
      (node (ref "U$4-Q1") (pin "P$2") (pinfunction "EMITTER_P$2") (pintype "bidirectional"))
      (node (ref "U$5-Q1") (pin "P$2") (pinfunction "EMITTER_P$2") (pintype "bidirectional"))
      (node (ref "XOR1-Q3") (pin "P$2") (pinfunction "EMITTER_P$2") (pintype "bidirectional"))
      (node (ref "XOR1-Q4") (pin "P$2") (pinfunction "EMITTER_P$2") (pintype "bidirectional"))
      (node (ref "XOR1-Q5") (pin "P$2") (pinfunction "EMITTER_P$2") (pintype "bidirectional"))
      (node (ref "XOR1-Q6") (pin "P$2") (pinfunction "EMITTER_P$2") (pintype "bidirectional"))
      (node (ref "XOR1-R3") (pin "1") (pinfunction "1_1") (pintype "passive"))
      (node (ref "XOR2-Q3") (pin "P$2") (pinfunction "EMITTER_P$2") (pintype "bidirectional"))
      (node (ref "XOR2-Q4") (pin "P$2") (pinfunction "EMITTER_P$2") (pintype "bidirectional"))
      (node (ref "XOR2-Q5") (pin "P$2") (pinfunction "EMITTER_P$2") (pintype "bidirectional"))
      (node (ref "XOR2-Q6") (pin "P$2") (pinfunction "EMITTER_P$2") (pintype "bidirectional"))
      (node (ref "XOR2-R3") (pin "1") (pinfunction "1_1") (pintype "passive"))
      (node (ref "XOR3-Q3") (pin "P$2") (pinfunction "EMITTER_P$2") (pintype "bidirectional"))
      (node (ref "XOR3-Q4") (pin "P$2") (pinfunction "EMITTER_P$2") (pintype "bidirectional"))
      (node (ref "XOR3-Q5") (pin "P$2") (pinfunction "EMITTER_P$2") (pintype "bidirectional"))
      (node (ref "XOR3-Q6") (pin "P$2") (pinfunction "EMITTER_P$2") (pintype "bidirectional"))
      (node (ref "XOR3-R3") (pin "1") (pinfunction "1_1") (pintype "passive"))
      (node (ref "XOR4-Q3") (pin "P$2") (pinfunction "EMITTER_P$2") (pintype "bidirectional"))
      (node (ref "XOR4-Q4") (pin "P$2") (pinfunction "EMITTER_P$2") (pintype "bidirectional"))
      (node (ref "XOR4-Q5") (pin "P$2") (pinfunction "EMITTER_P$2") (pintype "bidirectional"))
      (node (ref "XOR4-Q6") (pin "P$2") (pinfunction "EMITTER_P$2") (pintype "bidirectional"))
      (node (ref "XOR4-R3") (pin "1") (pinfunction "1_1") (pintype "passive"))
    )
    (net (code "17") (name "INVERT_OUT") (class "Default")
      (node (ref "CON2") (pin "7") (pinfunction "7_7") (pintype "passive"))
      (node (ref "XOR1-R2") (pin "1") (pinfunction "1_1") (pintype "passive"))
      (node (ref "XOR1-R5") (pin "1") (pinfunction "1_1") (pintype "passive"))
    )
    (net (code "18") (name "LEFT_A") (class "Default")
      (node (ref "CON2") (pin "11") (pinfunction "11_11") (pintype "passive"))
      (node (ref "SEL1-R7") (pin "1") (pinfunction "1_1") (pintype "passive"))
    )
    (net (code "19") (name "NOR") (class "Default")
      (node (ref "NOT1-R1") (pin "1") (pinfunction "1_1") (pintype "passive"))
      (node (ref "XOR2-Q3") (pin "P$3") (pinfunction "COLLECTOR_P$3") (pintype "bidirectional"))
      (node (ref "XOR2-Q4") (pin "P$3") (pinfunction "COLLECTOR_P$3") (pintype "bidirectional"))
      (node (ref "XOR2-R6") (pin "1") (pinfunction "1_1") (pintype "passive"))
      (node (ref "XOR2-R7") (pin "1") (pinfunction "1_1") (pintype "passive"))
    )
    (net (code "20") (name "Net-(L-A-PadC)") (class "Default")
      (node (ref "L-A") (pin "C") (pinfunction "C_C") (pintype "bidirectional"))
      (node (ref "U$1-R2") (pin "1") (pinfunction "1_1") (pintype "passive"))
    )
    (net (code "21") (name "Net-(L-B-PadC)") (class "Default")
      (node (ref "L-B") (pin "C") (pinfunction "C_C") (pintype "bidirectional"))
      (node (ref "U$2-R2") (pin "1") (pinfunction "1_1") (pintype "passive"))
    )
    (net (code "22") (name "Net-(L-C_IN-PadC)") (class "Default")
      (node (ref "L-C_IN") (pin "C") (pinfunction "C_C") (pintype "bidirectional"))
      (node (ref "U$3-R2") (pin "1") (pinfunction "1_1") (pintype "passive"))
    )
    (net (code "23") (name "Net-(L-C_OUT-PadC)") (class "Default")
      (node (ref "L-C_OUT") (pin "C") (pinfunction "C_C") (pintype "bidirectional"))
      (node (ref "U$5-R2") (pin "1") (pinfunction "1_1") (pintype "passive"))
    )
    (net (code "24") (name "Net-(L-R-PadC)") (class "Default")
      (node (ref "L-R") (pin "C") (pinfunction "C_C") (pintype "bidirectional"))
      (node (ref "U$4-R2") (pin "1") (pinfunction "1_1") (pintype "passive"))
    )
    (net (code "25") (name "Net-(L1-PadC)") (class "Default")
      (node (ref "L1") (pin "C") (pinfunction "C_C") (pintype "bidirectional"))
      (node (ref "R1") (pin "2") (pinfunction "2_2") (pintype "passive"))
    )
    (net (code "26") (name "Net-(NOT1-Q1-BASE)") (class "Default")
      (node (ref "NOT1-Q1") (pin "P$1") (pinfunction "BASE_P$1") (pintype "bidirectional"))
      (node (ref "NOT1-R1") (pin "2") (pinfunction "2_2") (pintype "passive"))
    )
    (net (code "27") (name "Net-(NOT1-Q1-COLLECTOR)") (class "Default")
      (node (ref "NOT1-Q1") (pin "P$3") (pinfunction "COLLECTOR_P$3") (pintype "bidirectional"))
      (node (ref "NOT1-R2") (pin "2") (pinfunction "2_2") (pintype "passive"))
      (node (ref "SEL3-R13") (pin "1") (pinfunction "1_1") (pintype "passive"))
    )
    (net (code "28") (name "Net-(OR1-Q1-BASE)") (class "Default")
      (node (ref "OR1-Q1") (pin "P$1") (pinfunction "BASE_P$1") (pintype "bidirectional"))
      (node (ref "OR1-R1") (pin "2") (pinfunction "2_2") (pintype "passive"))
    )
    (net (code "29") (name "Net-(OR1-Q1-COLLECTOR)") (class "Default")
      (node (ref "OR1-Q1") (pin "P$3") (pinfunction "COLLECTOR_P$3") (pintype "bidirectional"))
      (node (ref "OR1-Q2") (pin "P$3") (pinfunction "COLLECTOR_P$3") (pintype "bidirectional"))
      (node (ref "OR1-R3") (pin "1") (pinfunction "1_1") (pintype "passive"))
      (node (ref "OR1-R4") (pin "1") (pinfunction "1_1") (pintype "passive"))
    )
    (net (code "30") (name "Net-(OR1-Q2-BASE)") (class "Default")
      (node (ref "OR1-Q2") (pin "P$1") (pinfunction "BASE_P$1") (pintype "bidirectional"))
      (node (ref "OR1-R2") (pin "2") (pinfunction "2_2") (pintype "passive"))
    )
    (net (code "31") (name "Net-(OR1-Q3-BASE)") (class "Default")
      (node (ref "OR1-Q3") (pin "P$1") (pinfunction "BASE_P$1") (pintype "bidirectional"))
      (node (ref "OR1-R4") (pin "2") (pinfunction "2_2") (pintype "passive"))
    )
    (net (code "32") (name "Net-(OR2-Q1-BASE)") (class "Default")
      (node (ref "OR2-Q1") (pin "P$1") (pinfunction "BASE_P$1") (pintype "bidirectional"))
      (node (ref "OR2-R1") (pin "2") (pinfunction "2_2") (pintype "passive"))
    )
    (net (code "33") (name "Net-(OR2-Q1-COLLECTOR)") (class "Default")
      (node (ref "OR2-Q1") (pin "P$3") (pinfunction "COLLECTOR_P$3") (pintype "bidirectional"))
      (node (ref "OR2-Q2") (pin "P$3") (pinfunction "COLLECTOR_P$3") (pintype "bidirectional"))
      (node (ref "OR2-R3") (pin "1") (pinfunction "1_1") (pintype "passive"))
      (node (ref "OR2-R4") (pin "1") (pinfunction "1_1") (pintype "passive"))
    )
    (net (code "34") (name "Net-(OR2-Q2-BASE)") (class "Default")
      (node (ref "OR2-Q2") (pin "P$1") (pinfunction "BASE_P$1") (pintype "bidirectional"))
      (node (ref "OR2-R2") (pin "2") (pinfunction "2_2") (pintype "passive"))
    )
    (net (code "35") (name "Net-(OR2-Q3-BASE)") (class "Default")
      (node (ref "OR2-Q3") (pin "P$1") (pinfunction "BASE_P$1") (pintype "bidirectional"))
      (node (ref "OR2-R4") (pin "2") (pinfunction "2_2") (pintype "passive"))
    )
    (net (code "36") (name "Net-(SEL1-Q1-BASE)") (class "Default")
      (node (ref "SEL1-Q1") (pin "P$1") (pinfunction "BASE_P$1") (pintype "bidirectional"))
      (node (ref "SEL1-R2") (pin "2") (pinfunction "2_2") (pintype "passive"))
    )
    (net (code "37") (name "Net-(SEL1-Q1-COLLECTOR)") (class "Default")
      (node (ref "SEL1-Q1") (pin "P$3") (pinfunction "COLLECTOR_P$3") (pintype "bidirectional"))
      (node (ref "SEL1-Q5") (pin "P$3") (pinfunction "COLLECTOR_P$3") (pintype "bidirectional"))
      (node (ref "SEL1-R1") (pin "1") (pinfunction "1_1") (pintype "passive"))
      (node (ref "SEL1-R8") (pin "1") (pinfunction "1_1") (pintype "passive"))
    )
    (net (code "38") (name "Net-(SEL1-Q1-EMITTER)") (class "Default")
      (node (ref "SEL1-Q1") (pin "P$2") (pinfunction "EMITTER_P$2") (pintype "bidirectional"))
      (node (ref "SEL1-Q2") (pin "P$3") (pinfunction "COLLECTOR_P$3") (pintype "bidirectional"))
    )
    (net (code "39") (name "Net-(SEL1-Q2-BASE)") (class "Default")
      (node (ref "SEL1-Q2") (pin "P$1") (pinfunction "BASE_P$1") (pintype "bidirectional"))
      (node (ref "SEL1-R3") (pin "2") (pinfunction "2_2") (pintype "passive"))
    )
    (net (code "40") (name "Net-(SEL1-Q3-BASE)") (class "Default")
      (node (ref "SEL1-Q3") (pin "P$1") (pinfunction "BASE_P$1") (pintype "bidirectional"))
      (node (ref "SEL1-R5") (pin "2") (pinfunction "2_2") (pintype "passive"))
    )
    (net (code "41") (name "Net-(SEL1-Q3-COLLECTOR)") (class "Default")
      (node (ref "SEL1-Q3") (pin "P$3") (pinfunction "COLLECTOR_P$3") (pintype "bidirectional"))
      (node (ref "SEL1-R4") (pin "1") (pinfunction "1_1") (pintype "passive"))
      (node (ref "SEL1-R6") (pin "1") (pinfunction "1_1") (pintype "passive"))
    )
    (net (code "42") (name "Net-(SEL1-Q4-BASE)") (class "Default")
      (node (ref "SEL1-Q4") (pin "P$1") (pinfunction "BASE_P$1") (pintype "bidirectional"))
      (node (ref "SEL1-R7") (pin "2") (pinfunction "2_2") (pintype "passive"))
    )
    (net (code "43") (name "Net-(SEL1-Q4-COLLECTOR)") (class "Default")
      (node (ref "SEL1-Q4") (pin "P$3") (pinfunction "COLLECTOR_P$3") (pintype "bidirectional"))
      (node (ref "SEL1-Q5") (pin "P$2") (pinfunction "EMITTER_P$2") (pintype "bidirectional"))
    )
    (net (code "44") (name "Net-(SEL1-Q5-BASE)") (class "Default")
      (node (ref "SEL1-Q5") (pin "P$1") (pinfunction "BASE_P$1") (pintype "bidirectional"))
      (node (ref "SEL1-R6") (pin "2") (pinfunction "2_2") (pintype "passive"))
    )
    (net (code "45") (name "Net-(SEL1-Q6-BASE)") (class "Default")
      (node (ref "SEL1-Q6") (pin "P$1") (pinfunction "BASE_P$1") (pintype "bidirectional"))
      (node (ref "SEL1-R8") (pin "2") (pinfunction "2_2") (pintype "passive"))
    )
    (net (code "46") (name "Net-(SEL3-Q1-BASE)") (class "Default")
      (node (ref "SEL3-Q1") (pin "P$1") (pinfunction "BASE_P$1") (pintype "bidirectional"))
      (node (ref "SEL3-R2") (pin "2") (pinfunction "2_2") (pintype "passive"))
    )
    (net (code "47") (name "Net-(SEL3-Q1-COLLECTOR)") (class "Default")
      (node (ref "SEL3-Q1") (pin "P$3") (pinfunction "COLLECTOR_P$3") (pintype "bidirectional"))
      (node (ref "SEL3-Q11") (pin "P$3") (pinfunction "COLLECTOR_P$3") (pintype "bidirectional"))
      (node (ref "SEL3-Q13") (pin "P$3") (pinfunction "COLLECTOR_P$3") (pintype "bidirectional"))
      (node (ref "SEL3-Q3") (pin "P$3") (pinfunction "COLLECTOR_P$3") (pintype "bidirectional"))
      (node (ref "SEL3-Q5") (pin "P$3") (pinfunction "COLLECTOR_P$3") (pintype "bidirectional"))
      (node (ref "SEL3-Q7") (pin "P$3") (pinfunction "COLLECTOR_P$3") (pintype "bidirectional"))
      (node (ref "SEL3-Q9") (pin "P$3") (pinfunction "COLLECTOR_P$3") (pintype "bidirectional"))
      (node (ref "SEL3-R1") (pin "1") (pinfunction "1_1") (pintype "passive"))
      (node (ref "SEL3-R18") (pin "1") (pinfunction "1_1") (pintype "passive"))
    )
    (net (code "48") (name "Net-(SEL3-Q1-EMITTER)") (class "Default")
      (node (ref "SEL3-Q1") (pin "P$2") (pinfunction "EMITTER_P$2") (pintype "bidirectional"))
      (node (ref "SEL3-Q2") (pin "P$3") (pinfunction "COLLECTOR_P$3") (pintype "bidirectional"))
    )
    (net (code "49") (name "Net-(SEL3-Q2-BASE)") (class "Default")
      (node (ref "SEL3-Q2") (pin "P$1") (pinfunction "BASE_P$1") (pintype "bidirectional"))
      (node (ref "SEL3-R3") (pin "2") (pinfunction "2_2") (pintype "passive"))
    )
    (net (code "50") (name "Net-(SEL3-Q3-BASE)") (class "Default")
      (node (ref "SEL3-Q3") (pin "P$1") (pinfunction "BASE_P$1") (pintype "bidirectional"))
      (node (ref "SEL3-R4") (pin "2") (pinfunction "2_2") (pintype "passive"))
    )
    (net (code "51") (name "Net-(SEL3-Q3-EMITTER)") (class "Default")
      (node (ref "SEL3-Q3") (pin "P$2") (pinfunction "EMITTER_P$2") (pintype "bidirectional"))
      (node (ref "SEL3-Q4") (pin "P$3") (pinfunction "COLLECTOR_P$3") (pintype "bidirectional"))
    )
    (net (code "52") (name "Net-(SEL3-Q4-BASE)") (class "Default")
      (node (ref "SEL3-Q4") (pin "P$1") (pinfunction "BASE_P$1") (pintype "bidirectional"))
      (node (ref "SEL3-R5") (pin "2") (pinfunction "2_2") (pintype "passive"))
    )
    (net (code "53") (name "Net-(SEL3-Q5-BASE)") (class "Default")
      (node (ref "SEL3-Q5") (pin "P$1") (pinfunction "BASE_P$1") (pintype "bidirectional"))
      (node (ref "SEL3-R6") (pin "2") (pinfunction "2_2") (pintype "passive"))
    )
    (net (code "54") (name "Net-(SEL3-Q5-EMITTER)") (class "Default")
      (node (ref "SEL3-Q5") (pin "P$2") (pinfunction "EMITTER_P$2") (pintype "bidirectional"))
      (node (ref "SEL3-Q6") (pin "P$3") (pinfunction "COLLECTOR_P$3") (pintype "bidirectional"))
    )
    (net (code "55") (name "Net-(SEL3-Q6-BASE)") (class "Default")
      (node (ref "SEL3-Q6") (pin "P$1") (pinfunction "BASE_P$1") (pintype "bidirectional"))
      (node (ref "SEL3-R7") (pin "2") (pinfunction "2_2") (pintype "passive"))
    )
    (net (code "56") (name "Net-(SEL3-Q7-BASE)") (class "Default")
      (node (ref "SEL3-Q7") (pin "P$1") (pinfunction "BASE_P$1") (pintype "bidirectional"))
      (node (ref "SEL3-R8") (pin "2") (pinfunction "2_2") (pintype "passive"))
    )
    (net (code "57") (name "Net-(SEL3-Q7-EMITTER)") (class "Default")
      (node (ref "SEL3-Q7") (pin "P$2") (pinfunction "EMITTER_P$2") (pintype "bidirectional"))
      (node (ref "SEL3-Q8") (pin "P$3") (pinfunction "COLLECTOR_P$3") (pintype "bidirectional"))
    )
    (net (code "58") (name "Net-(SEL3-Q8-BASE)") (class "Default")
      (node (ref "SEL3-Q8") (pin "P$1") (pinfunction "BASE_P$1") (pintype "bidirectional"))
      (node (ref "SEL3-R9") (pin "2") (pinfunction "2_2") (pintype "passive"))
    )
    (net (code "59") (name "Net-(SEL3-Q9-BASE)") (class "Default")
      (node (ref "SEL3-Q9") (pin "P$1") (pinfunction "BASE_P$1") (pintype "bidirectional"))
      (node (ref "SEL3-R10") (pin "2") (pinfunction "2_2") (pintype "passive"))
    )
    (net (code "60") (name "Net-(SEL3-Q10-BASE)") (class "Default")
      (node (ref "SEL3-Q10") (pin "P$1") (pinfunction "BASE_P$1") (pintype "bidirectional"))
      (node (ref "SEL3-R11") (pin "2") (pinfunction "2_2") (pintype "passive"))
    )
    (net (code "61") (name "Net-(SEL3-Q10-COLLECTOR)") (class "Default")
      (node (ref "SEL3-Q10") (pin "P$3") (pinfunction "COLLECTOR_P$3") (pintype "bidirectional"))
      (node (ref "SEL3-Q9") (pin "P$2") (pinfunction "EMITTER_P$2") (pintype "bidirectional"))
    )
    (net (code "62") (name "Net-(SEL3-Q11-BASE)") (class "Default")
      (node (ref "SEL3-Q11") (pin "P$1") (pinfunction "BASE_P$1") (pintype "bidirectional"))
      (node (ref "SEL3-R12") (pin "2") (pinfunction "2_2") (pintype "passive"))
    )
    (net (code "63") (name "Net-(SEL3-Q11-EMITTER)") (class "Default")
      (node (ref "SEL3-Q11") (pin "P$2") (pinfunction "EMITTER_P$2") (pintype "bidirectional"))
      (node (ref "SEL3-Q12") (pin "P$3") (pinfunction "COLLECTOR_P$3") (pintype "bidirectional"))
    )
    (net (code "64") (name "Net-(SEL3-Q12-BASE)") (class "Default")
      (node (ref "SEL3-Q12") (pin "P$1") (pinfunction "BASE_P$1") (pintype "bidirectional"))
      (node (ref "SEL3-R13") (pin "2") (pinfunction "2_2") (pintype "passive"))
    )
    (net (code "65") (name "Net-(SEL3-Q13-BASE)") (class "Default")
      (node (ref "SEL3-Q13") (pin "P$1") (pinfunction "BASE_P$1") (pintype "bidirectional"))
      (node (ref "SEL3-R14") (pin "2") (pinfunction "2_2") (pintype "passive"))
    )
    (net (code "66") (name "Net-(SEL3-Q13-EMITTER)") (class "Default")
      (node (ref "SEL3-Q13") (pin "P$2") (pinfunction "EMITTER_P$2") (pintype "bidirectional"))
      (node (ref "SEL3-Q14") (pin "P$3") (pinfunction "COLLECTOR_P$3") (pintype "bidirectional"))
    )
    (net (code "67") (name "Net-(SEL3-Q14-BASE)") (class "Default")
      (node (ref "SEL3-Q14") (pin "P$1") (pinfunction "BASE_P$1") (pintype "bidirectional"))
      (node (ref "SEL3-R15") (pin "2") (pinfunction "2_2") (pintype "passive"))
    )
    (net (code "68") (name "Net-(SEL3-Q17-BASE)") (class "Default")
      (node (ref "SEL3-Q17") (pin "P$1") (pinfunction "BASE_P$1") (pintype "bidirectional"))
      (node (ref "SEL3-R18") (pin "2") (pinfunction "2_2") (pintype "passive"))
    )
    (net (code "69") (name "Net-(U$1-Q1-BASE)") (class "Default")
      (node (ref "U$1-Q1") (pin "P$1") (pinfunction "BASE_P$1") (pintype "bidirectional"))
      (node (ref "U$1-R1") (pin "2") (pinfunction "2_2") (pintype "passive"))
    )
    (net (code "70") (name "Net-(U$1-Q1-COLLECTOR)") (class "Default")
      (node (ref "U$1-Q1") (pin "P$3") (pinfunction "COLLECTOR_P$3") (pintype "bidirectional"))
      (node (ref "U$1-R2") (pin "2") (pinfunction "2_2") (pintype "passive"))
    )
    (net (code "71") (name "Net-(U$2-Q1-BASE)") (class "Default")
      (node (ref "U$2-Q1") (pin "P$1") (pinfunction "BASE_P$1") (pintype "bidirectional"))
      (node (ref "U$2-R1") (pin "2") (pinfunction "2_2") (pintype "passive"))
    )
    (net (code "72") (name "Net-(U$2-Q1-COLLECTOR)") (class "Default")
      (node (ref "U$2-Q1") (pin "P$3") (pinfunction "COLLECTOR_P$3") (pintype "bidirectional"))
      (node (ref "U$2-R2") (pin "2") (pinfunction "2_2") (pintype "passive"))
    )
    (net (code "73") (name "Net-(U$3-Q1-BASE)") (class "Default")
      (node (ref "U$3-Q1") (pin "P$1") (pinfunction "BASE_P$1") (pintype "bidirectional"))
      (node (ref "U$3-R1") (pin "2") (pinfunction "2_2") (pintype "passive"))
    )
    (net (code "74") (name "Net-(U$3-Q1-COLLECTOR)") (class "Default")
      (node (ref "U$3-Q1") (pin "P$3") (pinfunction "COLLECTOR_P$3") (pintype "bidirectional"))
      (node (ref "U$3-R2") (pin "2") (pinfunction "2_2") (pintype "passive"))
    )
    (net (code "75") (name "Net-(U$4-Q1-BASE)") (class "Default")
      (node (ref "U$4-Q1") (pin "P$1") (pinfunction "BASE_P$1") (pintype "bidirectional"))
      (node (ref "U$4-R1") (pin "2") (pinfunction "2_2") (pintype "passive"))
    )
    (net (code "76") (name "Net-(U$4-Q1-COLLECTOR)") (class "Default")
      (node (ref "U$4-Q1") (pin "P$3") (pinfunction "COLLECTOR_P$3") (pintype "bidirectional"))
      (node (ref "U$4-R2") (pin "2") (pinfunction "2_2") (pintype "passive"))
    )
    (net (code "77") (name "Net-(U$5-Q1-BASE)") (class "Default")
      (node (ref "U$5-Q1") (pin "P$1") (pinfunction "BASE_P$1") (pintype "bidirectional"))
      (node (ref "U$5-R1") (pin "2") (pinfunction "2_2") (pintype "passive"))
    )
    (net (code "78") (name "Net-(U$5-Q1-COLLECTOR)") (class "Default")
      (node (ref "U$5-Q1") (pin "P$3") (pinfunction "COLLECTOR_P$3") (pintype "bidirectional"))
      (node (ref "U$5-R2") (pin "2") (pinfunction "2_2") (pintype "passive"))
    )
    (net (code "79") (name "Net-(XOR1-Q1-BASE)") (class "Default")
      (node (ref "XOR1-Q1") (pin "P$1") (pinfunction "BASE_P$1") (pintype "bidirectional"))
      (node (ref "XOR1-R1") (pin "2") (pinfunction "2_2") (pintype "passive"))
    )
    (net (code "80") (name "Net-(XOR1-Q1-EMITTER)") (class "Default")
      (node (ref "XOR1-Q1") (pin "P$2") (pinfunction "EMITTER_P$2") (pintype "bidirectional"))
      (node (ref "XOR1-Q2") (pin "P$3") (pinfunction "COLLECTOR_P$3") (pintype "bidirectional"))
    )
    (net (code "81") (name "Net-(XOR1-Q2-BASE)") (class "Default")
      (node (ref "XOR1-Q2") (pin "P$1") (pinfunction "BASE_P$1") (pintype "bidirectional"))
      (node (ref "XOR1-R2") (pin "2") (pinfunction "2_2") (pintype "passive"))
    )
    (net (code "82") (name "Net-(XOR1-Q3-BASE)") (class "Default")
      (node (ref "XOR1-Q3") (pin "P$1") (pinfunction "BASE_P$1") (pintype "bidirectional"))
      (node (ref "XOR1-R5") (pin "2") (pinfunction "2_2") (pintype "passive"))
    )
    (net (code "83") (name "Net-(XOR1-Q4-BASE)") (class "Default")
      (node (ref "XOR1-Q4") (pin "P$1") (pinfunction "BASE_P$1") (pintype "bidirectional"))
      (node (ref "XOR1-R4") (pin "2") (pinfunction "2_2") (pintype "passive"))
    )
    (net (code "84") (name "Net-(XOR1-Q5-BASE)") (class "Default")
      (node (ref "XOR1-Q5") (pin "P$1") (pinfunction "BASE_P$1") (pintype "bidirectional"))
      (node (ref "XOR1-R7") (pin "2") (pinfunction "2_2") (pintype "passive"))
    )
    (net (code "85") (name "Net-(XOR1-Q6-BASE)") (class "Default")
      (node (ref "XOR1-Q6") (pin "P$1") (pinfunction "BASE_P$1") (pintype "bidirectional"))
      (node (ref "XOR1-R8") (pin "2") (pinfunction "2_2") (pintype "passive"))
    )
    (net (code "86") (name "Net-(XOR2-Q1-BASE)") (class "Default")
      (node (ref "XOR2-Q1") (pin "P$1") (pinfunction "BASE_P$1") (pintype "bidirectional"))
      (node (ref "XOR2-R1") (pin "2") (pinfunction "2_2") (pintype "passive"))
    )
    (net (code "87") (name "Net-(XOR2-Q1-EMITTER)") (class "Default")
      (node (ref "XOR2-Q1") (pin "P$2") (pinfunction "EMITTER_P$2") (pintype "bidirectional"))
      (node (ref "XOR2-Q2") (pin "P$3") (pinfunction "COLLECTOR_P$3") (pintype "bidirectional"))
    )
    (net (code "88") (name "Net-(XOR2-Q2-BASE)") (class "Default")
      (node (ref "XOR2-Q2") (pin "P$1") (pinfunction "BASE_P$1") (pintype "bidirectional"))
      (node (ref "XOR2-R2") (pin "2") (pinfunction "2_2") (pintype "passive"))
    )
    (net (code "89") (name "Net-(XOR2-Q3-BASE)") (class "Default")
      (node (ref "XOR2-Q3") (pin "P$1") (pinfunction "BASE_P$1") (pintype "bidirectional"))
      (node (ref "XOR2-R5") (pin "2") (pinfunction "2_2") (pintype "passive"))
    )
    (net (code "90") (name "Net-(XOR2-Q4-BASE)") (class "Default")
      (node (ref "XOR2-Q4") (pin "P$1") (pinfunction "BASE_P$1") (pintype "bidirectional"))
      (node (ref "XOR2-R4") (pin "2") (pinfunction "2_2") (pintype "passive"))
    )
    (net (code "91") (name "Net-(XOR2-Q5-BASE)") (class "Default")
      (node (ref "XOR2-Q5") (pin "P$1") (pinfunction "BASE_P$1") (pintype "bidirectional"))
      (node (ref "XOR2-R7") (pin "2") (pinfunction "2_2") (pintype "passive"))
    )
    (net (code "92") (name "Net-(XOR2-Q6-BASE)") (class "Default")
      (node (ref "XOR2-Q6") (pin "P$1") (pinfunction "BASE_P$1") (pintype "bidirectional"))
      (node (ref "XOR2-R8") (pin "2") (pinfunction "2_2") (pintype "passive"))
    )
    (net (code "93") (name "Net-(XOR3-Q1-BASE)") (class "Default")
      (node (ref "XOR3-Q1") (pin "P$1") (pinfunction "BASE_P$1") (pintype "bidirectional"))
      (node (ref "XOR3-R1") (pin "2") (pinfunction "2_2") (pintype "passive"))
    )
    (net (code "94") (name "Net-(XOR3-Q1-EMITTER)") (class "Default")
      (node (ref "XOR3-Q1") (pin "P$2") (pinfunction "EMITTER_P$2") (pintype "bidirectional"))
      (node (ref "XOR3-Q2") (pin "P$3") (pinfunction "COLLECTOR_P$3") (pintype "bidirectional"))
    )
    (net (code "95") (name "Net-(XOR3-Q2-BASE)") (class "Default")
      (node (ref "XOR3-Q2") (pin "P$1") (pinfunction "BASE_P$1") (pintype "bidirectional"))
      (node (ref "XOR3-R2") (pin "2") (pinfunction "2_2") (pintype "passive"))
    )
    (net (code "96") (name "Net-(XOR3-Q3-BASE)") (class "Default")
      (node (ref "XOR3-Q3") (pin "P$1") (pinfunction "BASE_P$1") (pintype "bidirectional"))
      (node (ref "XOR3-R5") (pin "2") (pinfunction "2_2") (pintype "passive"))
    )
    (net (code "97") (name "Net-(XOR3-Q4-BASE)") (class "Default")
      (node (ref "XOR3-Q4") (pin "P$1") (pinfunction "BASE_P$1") (pintype "bidirectional"))
      (node (ref "XOR3-R4") (pin "2") (pinfunction "2_2") (pintype "passive"))
    )
    (net (code "98") (name "Net-(XOR3-Q5-BASE)") (class "Default")
      (node (ref "XOR3-Q5") (pin "P$1") (pinfunction "BASE_P$1") (pintype "bidirectional"))
      (node (ref "XOR3-R7") (pin "2") (pinfunction "2_2") (pintype "passive"))
    )
    (net (code "99") (name "Net-(XOR3-Q6-BASE)") (class "Default")
      (node (ref "XOR3-Q6") (pin "P$1") (pinfunction "BASE_P$1") (pintype "bidirectional"))
      (node (ref "XOR3-R8") (pin "2") (pinfunction "2_2") (pintype "passive"))
    )
    (net (code "100") (name "Net-(XOR4-Q1-BASE)") (class "Default")
      (node (ref "XOR4-Q1") (pin "P$1") (pinfunction "BASE_P$1") (pintype "bidirectional"))
      (node (ref "XOR4-R1") (pin "2") (pinfunction "2_2") (pintype "passive"))
    )
    (net (code "101") (name "Net-(XOR4-Q1-EMITTER)") (class "Default")
      (node (ref "XOR4-Q1") (pin "P$2") (pinfunction "EMITTER_P$2") (pintype "bidirectional"))
      (node (ref "XOR4-Q2") (pin "P$3") (pinfunction "COLLECTOR_P$3") (pintype "bidirectional"))
    )
    (net (code "102") (name "Net-(XOR4-Q2-BASE)") (class "Default")
      (node (ref "XOR4-Q2") (pin "P$1") (pinfunction "BASE_P$1") (pintype "bidirectional"))
      (node (ref "XOR4-R2") (pin "2") (pinfunction "2_2") (pintype "passive"))
    )
    (net (code "103") (name "Net-(XOR4-Q3-BASE)") (class "Default")
      (node (ref "XOR4-Q3") (pin "P$1") (pinfunction "BASE_P$1") (pintype "bidirectional"))
      (node (ref "XOR4-R5") (pin "2") (pinfunction "2_2") (pintype "passive"))
    )
    (net (code "104") (name "Net-(XOR4-Q4-BASE)") (class "Default")
      (node (ref "XOR4-Q4") (pin "P$1") (pinfunction "BASE_P$1") (pintype "bidirectional"))
      (node (ref "XOR4-R4") (pin "2") (pinfunction "2_2") (pintype "passive"))
    )
    (net (code "105") (name "Net-(XOR4-Q5-BASE)") (class "Default")
      (node (ref "XOR4-Q5") (pin "P$1") (pinfunction "BASE_P$1") (pintype "bidirectional"))
      (node (ref "XOR4-R7") (pin "2") (pinfunction "2_2") (pintype "passive"))
    )
    (net (code "106") (name "Net-(XOR4-Q6-BASE)") (class "Default")
      (node (ref "XOR4-Q6") (pin "P$1") (pinfunction "BASE_P$1") (pintype "bidirectional"))
      (node (ref "XOR4-R8") (pin "2") (pinfunction "2_2") (pintype "passive"))
    )
    (net (code "107") (name "RESULT") (class "Default")
      (node (ref "CON2") (pin "18") (pinfunction "18_18") (pintype "passive"))
      (node (ref "U$4-R1") (pin "1") (pinfunction "1_1") (pintype "passive"))
      (node (ref "XOR1-Q5") (pin "P$3") (pinfunction "COLLECTOR_P$3") (pintype "bidirectional"))
      (node (ref "XOR1-Q6") (pin "P$3") (pinfunction "COLLECTOR_P$3") (pintype "bidirectional"))
      (node (ref "XOR1-R9") (pin "1") (pinfunction "1_1") (pintype "passive"))
    )
    (net (code "108") (name "RIGHT_A") (class "Default")
      (node (ref "CON2") (pin "13") (pinfunction "13_13") (pintype "passive"))
      (node (ref "SEL1-R3") (pin "1") (pinfunction "1_1") (pintype "passive"))
    )
    (net (code "109") (name "SUBTRACT") (class "Default")
      (node (ref "CON2") (pin "9") (pinfunction "9_9") (pintype "passive"))
      (node (ref "SEL1-R2") (pin "1") (pinfunction "1_1") (pintype "passive"))
      (node (ref "SEL1-R5") (pin "1") (pinfunction "1_1") (pintype "passive"))
      (node (ref "XOR4-R2") (pin "1") (pinfunction "1_1") (pintype "passive"))
      (node (ref "XOR4-R5") (pin "1") (pinfunction "1_1") (pintype "passive"))
    )
    (net (code "110") (name "SUM") (class "Default")
      (node (ref "OR2-R2") (pin "1") (pinfunction "1_1") (pintype "passive"))
      (node (ref "SEL3-R9") (pin "1") (pinfunction "1_1") (pintype "passive"))
      (node (ref "XOR3-Q5") (pin "P$3") (pinfunction "COLLECTOR_P$3") (pintype "bidirectional"))
      (node (ref "XOR3-Q6") (pin "P$3") (pinfunction "COLLECTOR_P$3") (pintype "bidirectional"))
      (node (ref "XOR3-R9") (pin "1") (pinfunction "1_1") (pintype "passive"))
    )
    (net (code "111") (name "S_ADD") (class "Default")
      (node (ref "CON2") (pin "8") (pinfunction "8_8") (pintype "passive"))
      (node (ref "SEL3-R8") (pin "1") (pinfunction "1_1") (pintype "passive"))
    )
    (net (code "112") (name "S_AND") (class "Default")
      (node (ref "CON2") (pin "6") (pinfunction "6_6") (pintype "passive"))
      (node (ref "SEL3-R14") (pin "1") (pinfunction "1_1") (pintype "passive"))
    )
    (net (code "113") (name "S_ID") (class "Default")
      (node (ref "CON2") (pin "4") (pinfunction "4_4") (pintype "passive"))
      (node (ref "SEL3-R6") (pin "1") (pinfunction "1_1") (pintype "passive"))
    )
    (net (code "114") (name "S_LOAD") (class "Default")
      (node (ref "CON2") (pin "16") (pinfunction "16_16") (pintype "passive"))
      (node (ref "SEL3-R4") (pin "1") (pinfunction "1_1") (pintype "passive"))
    )
    (net (code "115") (name "S_OR") (class "Default")
      (node (ref "CON2") (pin "10") (pinfunction "10_10") (pintype "passive"))
      (node (ref "SEL3-R12") (pin "1") (pinfunction "1_1") (pintype "passive"))
    )
    (net (code "116") (name "S_SHIFT") (class "Default")
      (node (ref "CON2") (pin "14") (pinfunction "14_14") (pintype "passive"))
      (node (ref "SEL3-R2") (pin "1") (pinfunction "1_1") (pintype "passive"))
    )
    (net (code "117") (name "S_XOR") (class "Default")
      (node (ref "CON2") (pin "12") (pinfunction "12_12") (pintype "passive"))
      (node (ref "SEL3-R10") (pin "1") (pinfunction "1_1") (pintype "passive"))
    )
    (net (code "118") (name "XOR") (class "Default")
      (node (ref "SEL3-R11") (pin "1") (pinfunction "1_1") (pintype "passive"))
      (node (ref "XOR2-Q5") (pin "P$3") (pinfunction "COLLECTOR_P$3") (pintype "bidirectional"))
      (node (ref "XOR2-Q6") (pin "P$3") (pinfunction "COLLECTOR_P$3") (pintype "bidirectional"))
      (node (ref "XOR2-R9") (pin "1") (pinfunction "1_1") (pintype "passive"))
      (node (ref "XOR3-R2") (pin "1") (pinfunction "1_1") (pintype "passive"))
      (node (ref "XOR3-R5") (pin "1") (pinfunction "1_1") (pintype "passive"))
    )
    (net (code "119") (name "_EQUAL_IN") (class "Default")
      (node (ref "CON2") (pin "15") (pinfunction "15_15") (pintype "passive"))
      (node (ref "OR2-R1") (pin "1") (pinfunction "1_1") (pintype "passive"))
    )
    (net (code "120") (name "_EQUAL_OUT") (class "Default")
      (node (ref "CON2") (pin "19") (pinfunction "19_19") (pintype "passive"))
      (node (ref "OR2-Q3") (pin "P$3") (pinfunction "COLLECTOR_P$3") (pintype "bidirectional"))
      (node (ref "OR2-R5") (pin "1") (pinfunction "1_1") (pintype "passive"))
    )
  )
)
